# M706H.net
KiCad netlist of a schematic drawn in EAGLE
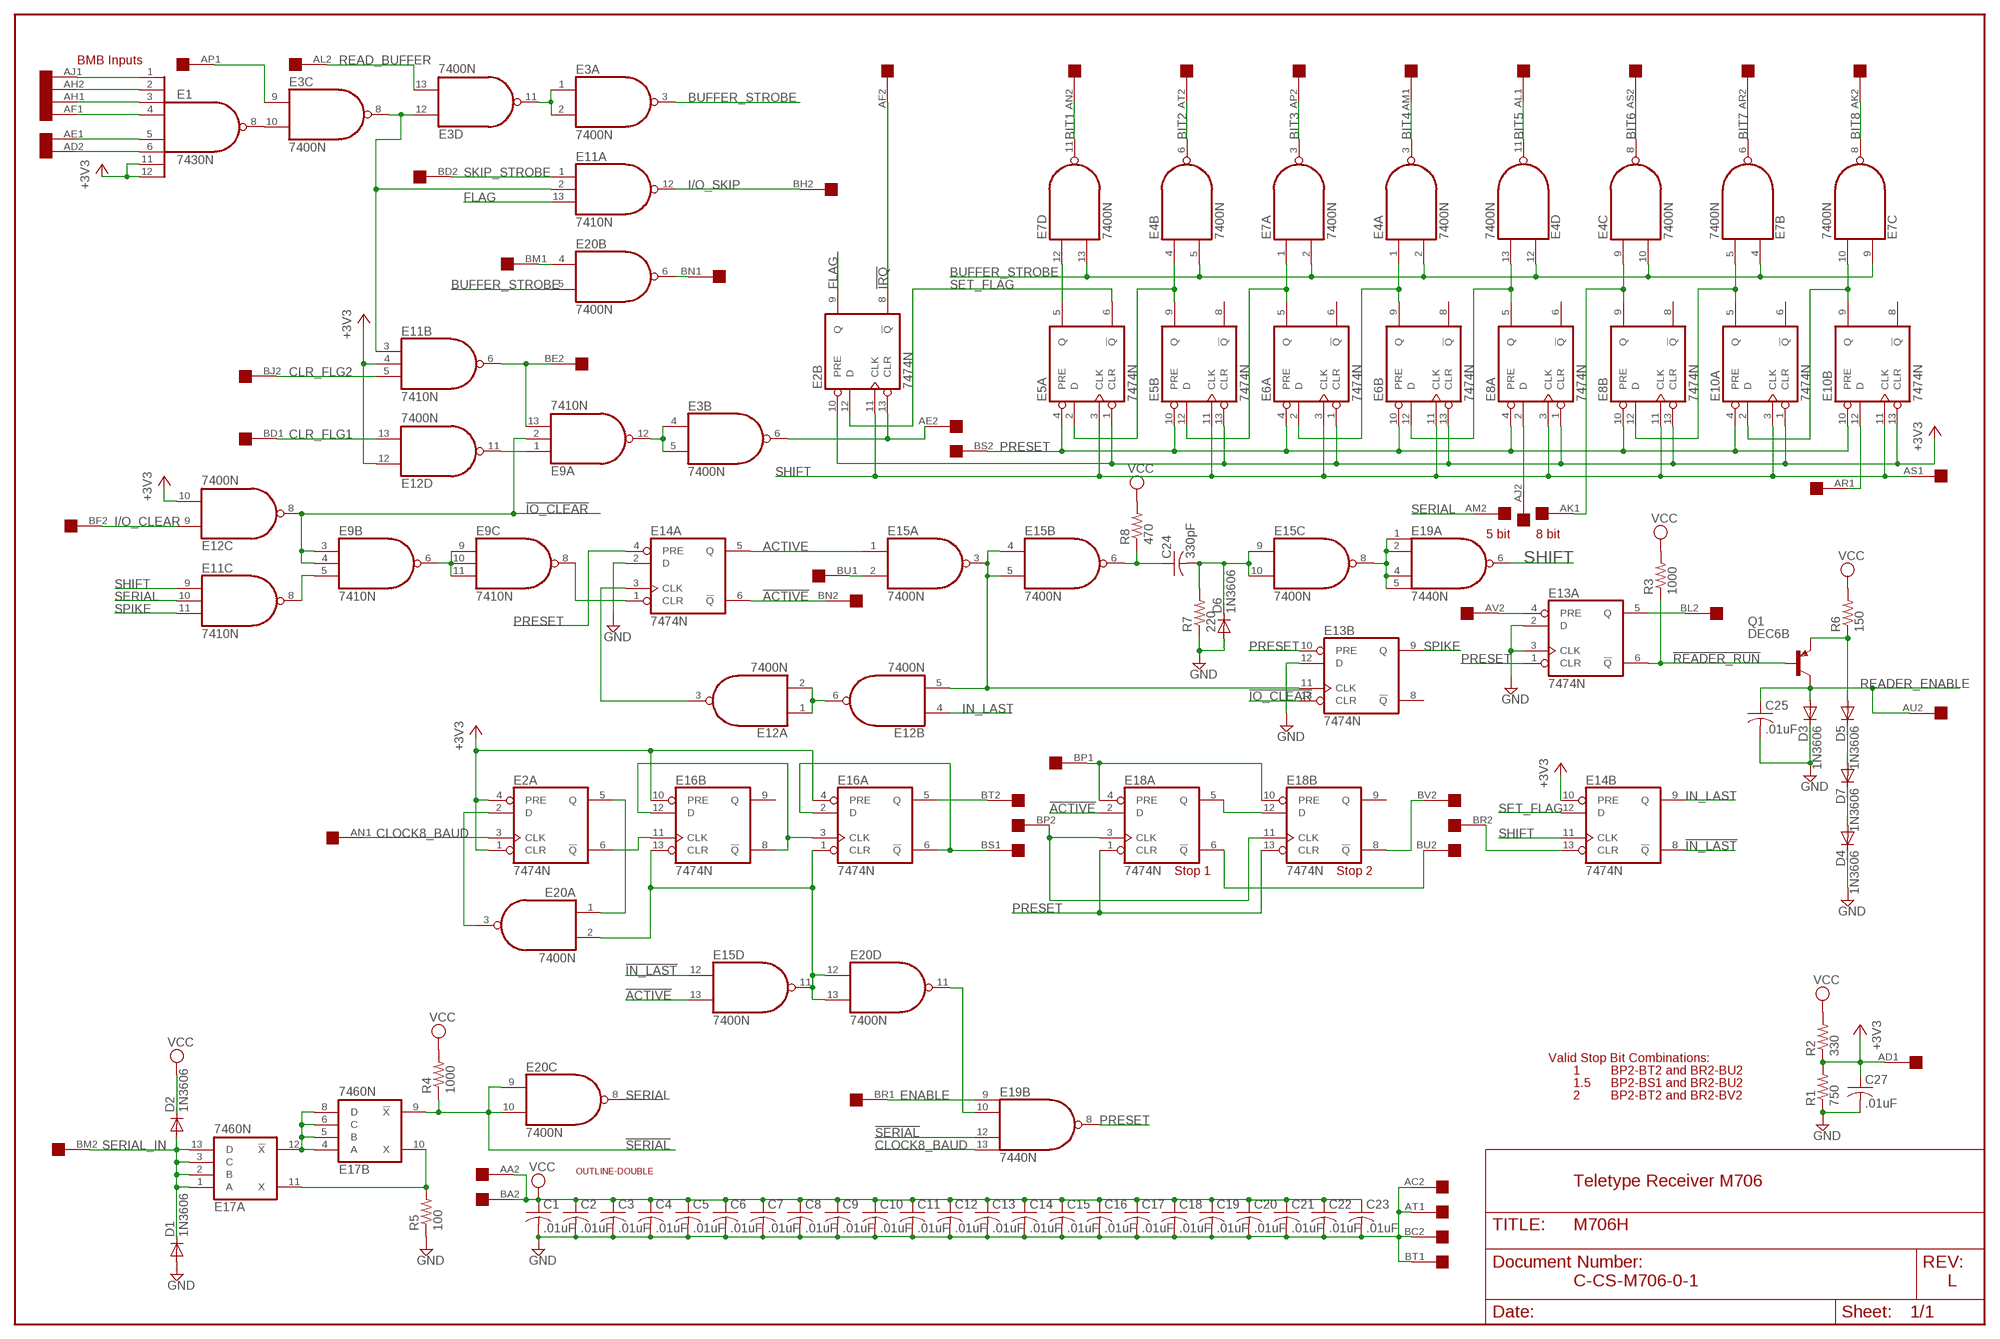
[diagram p0: schematic, sheet 1]

(export (version "E")
  (design (tool "Eeschema 10.0.6"))
  (components
    (comp (ref "C1")
      (value ".01uF")
      (footprint "eagle-import:C050-025X075")
      (libsource (lib "eagle-import") (part "C-US050-025X075"))
    )
    (comp (ref "C2")
      (value ".01uF")
      (footprint "eagle-import:C050-025X075")
      (libsource (lib "eagle-import") (part "C-US050-025X075"))
    )
    (comp (ref "C3")
      (value ".01uF")
      (footprint "eagle-import:C050-025X075")
      (libsource (lib "eagle-import") (part "C-US050-025X075"))
    )
    (comp (ref "C4")
      (value ".01uF")
      (footprint "eagle-import:C050-025X075")
      (libsource (lib "eagle-import") (part "C-US050-025X075"))
    )
    (comp (ref "C5")
      (value ".01uF")
      (footprint "eagle-import:C050-025X075")
      (libsource (lib "eagle-import") (part "C-US050-025X075"))
    )
    (comp (ref "C6")
      (value ".01uF")
      (footprint "eagle-import:C050-025X075")
      (libsource (lib "eagle-import") (part "C-US050-025X075"))
    )
    (comp (ref "C7")
      (value ".01uF")
      (footprint "eagle-import:C050-025X075")
      (libsource (lib "eagle-import") (part "C-US050-025X075"))
    )
    (comp (ref "C8")
      (value ".01uF")
      (footprint "eagle-import:C050-025X075")
      (libsource (lib "eagle-import") (part "C-US050-025X075"))
    )
    (comp (ref "C9")
      (value ".01uF")
      (footprint "eagle-import:C050-025X075")
      (libsource (lib "eagle-import") (part "C-US050-025X075"))
    )
    (comp (ref "C10")
      (value ".01uF")
      (footprint "eagle-import:C050-025X075")
      (libsource (lib "eagle-import") (part "C-US050-025X075"))
    )
    (comp (ref "C11")
      (value ".01uF")
      (footprint "eagle-import:C050-025X075")
      (libsource (lib "eagle-import") (part "C-US050-025X075"))
    )
    (comp (ref "C12")
      (value ".01uF")
      (footprint "eagle-import:C050-025X075")
      (libsource (lib "eagle-import") (part "C-US050-025X075"))
    )
    (comp (ref "C13")
      (value ".01uF")
      (footprint "eagle-import:C050-025X075")
      (libsource (lib "eagle-import") (part "C-US050-025X075"))
    )
    (comp (ref "C14")
      (value ".01uF")
      (footprint "eagle-import:C050-025X075")
      (libsource (lib "eagle-import") (part "C-US050-025X075"))
    )
    (comp (ref "C15")
      (value ".01uF")
      (footprint "eagle-import:C050-025X075")
      (libsource (lib "eagle-import") (part "C-US050-025X075"))
    )
    (comp (ref "C16")
      (value ".01uF")
      (footprint "eagle-import:C050-025X075")
      (libsource (lib "eagle-import") (part "C-US050-025X075"))
    )
    (comp (ref "C17")
      (value ".01uF")
      (footprint "eagle-import:C050-025X075")
      (libsource (lib "eagle-import") (part "C-US050-025X075"))
    )
    (comp (ref "C18")
      (value ".01uF")
      (footprint "eagle-import:C050-025X075")
      (libsource (lib "eagle-import") (part "C-US050-025X075"))
    )
    (comp (ref "C19")
      (value ".01uF")
      (footprint "eagle-import:C050-025X075")
      (libsource (lib "eagle-import") (part "C-US050-025X075"))
    )
    (comp (ref "C20")
      (value ".01uF")
      (footprint "eagle-import:C050-025X075")
      (libsource (lib "eagle-import") (part "C-US050-025X075"))
    )
    (comp (ref "C21")
      (value ".01uF")
      (footprint "eagle-import:C050-025X075")
      (libsource (lib "eagle-import") (part "C-US050-025X075"))
    )
    (comp (ref "C22")
      (value ".01uF")
      (footprint "eagle-import:C050-025X075")
      (libsource (lib "eagle-import") (part "C-US050-025X075"))
    )
    (comp (ref "C23")
      (value ".01uF")
      (footprint "eagle-import:C050-025X075")
      (libsource (lib "eagle-import") (part "C-US050-025X075"))
    )
    (comp (ref "C24")
      (value "330pF")
      (footprint "eagle-import:C050-025X075")
      (libsource (lib "eagle-import") (part "C-US050-025X075"))
    )
    (comp (ref "C25")
      (value ".01uF")
      (footprint "eagle-import:C050-025X075")
      (libsource (lib "eagle-import") (part "C-US050-025X075"))
    )
    (comp (ref "C27")
      (value ".01uF")
      (footprint "eagle-import:C050-025X075")
      (libsource (lib "eagle-import") (part "C-US050-025X075"))
    )
    (comp (ref "D1")
      (value "1N3606")
      (footprint "eagle-import:DO35-10")
      (libsource (lib "eagle-import") (part "1N4148DO35-10"))
    )
    (comp (ref "D2")
      (value "1N3606")
      (footprint "eagle-import:DO35-10")
      (libsource (lib "eagle-import") (part "1N4148DO35-10"))
    )
    (comp (ref "D3")
      (value "1N3606")
      (footprint "eagle-import:DO35-10")
      (libsource (lib "eagle-import") (part "1N4148DO35-10"))
    )
    (comp (ref "D4")
      (value "1N3606")
      (footprint "eagle-import:DO35-10")
      (libsource (lib "eagle-import") (part "1N4148DO35-10"))
    )
    (comp (ref "D5")
      (value "1N3606")
      (footprint "eagle-import:DO35-10")
      (libsource (lib "eagle-import") (part "1N4148DO35-10"))
    )
    (comp (ref "D6")
      (value "1N3606")
      (footprint "eagle-import:DO35-10")
      (libsource (lib "eagle-import") (part "1N4148DO35-10"))
    )
    (comp (ref "D7")
      (value "1N3606")
      (footprint "eagle-import:DO35-10")
      (libsource (lib "eagle-import") (part "1N4148DO35-10"))
    )
    (comp (ref "E1")
      (value "7430N")
      (footprint "eagle-import:DIL14")
      (libsource (lib "eagle-import") (part "7430N"))
    )
    (comp (ref "E2")
      (value "7474N")
      (footprint "eagle-import:DIL14")
      (libsource (lib "eagle-import") (part "7474NS"))
    )
    (comp (ref "E3")
      (value "7400N")
      (footprint "eagle-import:DIL14")
      (libsource (lib "eagle-import") (part "7400N"))
    )
    (comp (ref "E4")
      (value "7400N")
      (footprint "eagle-import:DIL14")
      (libsource (lib "eagle-import") (part "7400N"))
    )
    (comp (ref "E5")
      (value "7474N")
      (footprint "eagle-import:DIL14")
      (libsource (lib "eagle-import") (part "7474NS"))
    )
    (comp (ref "E6")
      (value "7474N")
      (footprint "eagle-import:DIL14")
      (libsource (lib "eagle-import") (part "7474NS"))
    )
    (comp (ref "E7")
      (value "7400N")
      (footprint "eagle-import:DIL14")
      (libsource (lib "eagle-import") (part "7400N"))
    )
    (comp (ref "E8")
      (value "7474N")
      (footprint "eagle-import:DIL14")
      (libsource (lib "eagle-import") (part "7474NS"))
    )
    (comp (ref "E9")
      (value "7410N")
      (footprint "eagle-import:DIL14")
      (libsource (lib "eagle-import") (part "7410N"))
    )
    (comp (ref "E10")
      (value "7474N")
      (footprint "eagle-import:DIL14")
      (libsource (lib "eagle-import") (part "7474NS"))
    )
    (comp (ref "E11")
      (value "7410N")
      (footprint "eagle-import:DIL14")
      (libsource (lib "eagle-import") (part "7410N"))
    )
    (comp (ref "E12")
      (value "7400N")
      (footprint "eagle-import:DIL14")
      (libsource (lib "eagle-import") (part "7400N"))
    )
    (comp (ref "E13")
      (value "7474N")
      (footprint "eagle-import:DIL14")
      (libsource (lib "eagle-import") (part "7474NS"))
    )
    (comp (ref "E14")
      (value "7474N")
      (footprint "eagle-import:DIL14")
      (libsource (lib "eagle-import") (part "7474NS"))
    )
    (comp (ref "E15")
      (value "7400N")
      (footprint "eagle-import:DIL14")
      (libsource (lib "eagle-import") (part "7400N"))
    )
    (comp (ref "E16")
      (value "7474N")
      (footprint "eagle-import:DIL14")
      (libsource (lib "eagle-import") (part "7474NS"))
    )
    (comp (ref "E17")
      (value "7460N")
      (footprint "eagle-import:DIL14")
      (libsource (lib "eagle-import") (part "7460N"))
    )
    (comp (ref "E18")
      (value "7474N")
      (footprint "eagle-import:DIL14")
      (libsource (lib "eagle-import") (part "7474NS"))
    )
    (comp (ref "E19")
      (value "7440N")
      (footprint "eagle-import:DIL14")
      (libsource (lib "eagle-import") (part "7420NS"))
    )
    (comp (ref "E20")
      (value "7400N")
      (footprint "eagle-import:DIL14")
      (libsource (lib "eagle-import") (part "7400N"))
    )
    (comp (ref "Q1")
      (value "DEC6B")
      (footprint "eagle-import:TO39")
      (libsource (lib "eagle-import") (part "2N2904"))
    )
    (comp (ref "R1")
      (value "750")
      (footprint "eagle-import:0207_10")
      (libsource (lib "eagle-import") (part "R-US_0207/10"))
    )
    (comp (ref "R2")
      (value "330")
      (footprint "eagle-import:0207_10")
      (libsource (lib "eagle-import") (part "R-US_0207/10"))
    )
    (comp (ref "R3")
      (value "1000")
      (footprint "eagle-import:0207_10")
      (libsource (lib "eagle-import") (part "R-US_0207/10"))
    )
    (comp (ref "R4")
      (value "1000")
      (footprint "eagle-import:0207_10")
      (libsource (lib "eagle-import") (part "R-US_0207/10"))
    )
    (comp (ref "R5")
      (value "100")
      (footprint "eagle-import:0207_10")
      (libsource (lib "eagle-import") (part "R-US_0207/10"))
    )
    (comp (ref "R6")
      (value "150")
      (footprint "eagle-import:0207_10")
      (libsource (lib "eagle-import") (part "R-US_0207/10"))
    )
    (comp (ref "R7")
      (value "220")
      (footprint "eagle-import:0207_10")
      (libsource (lib "eagle-import") (part "R-US_0207/10"))
    )
    (comp (ref "R8")
      (value "470")
      (footprint "eagle-import:0207_10")
      (libsource (lib "eagle-import") (part "R-US_0207/10"))
    )
    (comp (ref "U$1")
      (value "OUTLINE-DOUBLE")
      (footprint "eagle-import:DOUBLE")
      (libsource (lib "eagle-import") (part "OUTLINE-DOUBLE"))
    )
    (comp (ref "U$2")
      (value "DOUBLE")
      (footprint "eagle-import:EDGE-CON4")
      (libsource (lib "eagle-import") (part "DOUBLE"))
    )
  )
  (nets
    (net (code "1") (name "+3V3") (class "Default")
      (node (ref "C27") (pin "1") (pinfunction "1_1") (pintype "passive"))
      (node (ref "E1") (pin "11") (pinfunction "I6_11") (pintype "input"))
      (node (ref "E1") (pin "12") (pinfunction "I7_12") (pintype "input"))
      (node (ref "E10") (pin "1") (pinfunction "CLR_1") (pintype "input"))
      (node (ref "E10") (pin "13") (pinfunction "CLR_13") (pintype "input"))
      (node (ref "E11") (pin "4") (pinfunction "I1_4") (pintype "input"))
      (node (ref "E12") (pin "10") (pinfunction "I1_10") (pintype "input"))
      (node (ref "E12") (pin "12") (pinfunction "I0_12") (pintype "input"))
      (node (ref "E14") (pin "10") (pinfunction "PRE_10") (pintype "input"))
      (node (ref "E16") (pin "10") (pinfunction "PRE_10") (pintype "input"))
      (node (ref "E16") (pin "4") (pinfunction "PRE_4") (pintype "input"))
      (node (ref "E2") (pin "1") (pinfunction "CLR_1") (pintype "input"))
      (node (ref "E2") (pin "10") (pinfunction "PRE_10") (pintype "input"))
      (node (ref "E2") (pin "4") (pinfunction "PRE_4") (pintype "input"))
      (node (ref "E5") (pin "1") (pinfunction "CLR_1") (pintype "input"))
      (node (ref "E5") (pin "13") (pinfunction "CLR_13") (pintype "input"))
      (node (ref "E6") (pin "1") (pinfunction "CLR_1") (pintype "input"))
      (node (ref "E6") (pin "13") (pinfunction "CLR_13") (pintype "input"))
      (node (ref "E8") (pin "1") (pinfunction "CLR_1") (pintype "input"))
      (node (ref "E8") (pin "13") (pinfunction "CLR_13") (pintype "input"))
      (node (ref "R1") (pin "2") (pinfunction "2_2") (pintype "passive"))
      (node (ref "R2") (pin "1") (pinfunction "1_1") (pintype "passive"))
      (node (ref "U$2") (pin "AD1") (pinfunction "1_AD1") (pintype "bidirectional"))
    )
    (net (code "2") (name "/ACTIVE") (class "Default")
      (node (ref "E14") (pin "5") (pinfunction "Q_5") (pintype "output"))
      (node (ref "E15") (pin "1") (pinfunction "I0_1") (pintype "input"))
    )
    (net (code "3") (name "/BIT1") (class "Default")
      (node (ref "E7") (pin "11") (pinfunction "O_11") (pintype "output"))
      (node (ref "U$2") (pin "AN2") (pinfunction "1_AN2") (pintype "bidirectional"))
    )
    (net (code "4") (name "/BIT2") (class "Default")
      (node (ref "E4") (pin "6") (pinfunction "O_6") (pintype "output"))
      (node (ref "U$2") (pin "AT2") (pinfunction "1_AT2") (pintype "bidirectional"))
    )
    (net (code "5") (name "/BIT3") (class "Default")
      (node (ref "E7") (pin "3") (pinfunction "O_3") (pintype "output"))
      (node (ref "U$2") (pin "AP2") (pinfunction "1_AP2") (pintype "bidirectional"))
    )
    (net (code "6") (name "/BIT4") (class "Default")
      (node (ref "E4") (pin "3") (pinfunction "O_3") (pintype "output"))
      (node (ref "U$2") (pin "AM1") (pinfunction "1_AM1") (pintype "bidirectional"))
    )
    (net (code "7") (name "/BIT5") (class "Default")
      (node (ref "E4") (pin "11") (pinfunction "O_11") (pintype "output"))
      (node (ref "U$2") (pin "AL1") (pinfunction "1_AL1") (pintype "bidirectional"))
    )
    (net (code "8") (name "/BIT6") (class "Default")
      (node (ref "E4") (pin "8") (pinfunction "O_8") (pintype "output"))
      (node (ref "U$2") (pin "AS2") (pinfunction "1_AS2") (pintype "bidirectional"))
    )
    (net (code "9") (name "/BIT7") (class "Default")
      (node (ref "E7") (pin "6") (pinfunction "O_6") (pintype "output"))
      (node (ref "U$2") (pin "AR2") (pinfunction "1_AR2") (pintype "bidirectional"))
    )
    (net (code "10") (name "/BIT8") (class "Default")
      (node (ref "E7") (pin "8") (pinfunction "O_8") (pintype "output"))
      (node (ref "U$2") (pin "AK2") (pinfunction "1_AK2") (pintype "bidirectional"))
    )
    (net (code "11") (name "/BUFFER_STROBE") (class "Default")
      (node (ref "E20") (pin "5") (pinfunction "I1_5") (pintype "input"))
      (node (ref "E3") (pin "3") (pinfunction "O_3") (pintype "output"))
      (node (ref "E4") (pin "10") (pinfunction "I1_10") (pintype "input"))
      (node (ref "E4") (pin "12") (pinfunction "I0_12") (pintype "input"))
      (node (ref "E4") (pin "2") (pinfunction "I1_2") (pintype "input"))
      (node (ref "E4") (pin "5") (pinfunction "I1_5") (pintype "input"))
      (node (ref "E7") (pin "13") (pinfunction "I1_13") (pintype "input"))
      (node (ref "E7") (pin "2") (pinfunction "I1_2") (pintype "input"))
      (node (ref "E7") (pin "4") (pinfunction "I0_4") (pintype "input"))
      (node (ref "E7") (pin "9") (pinfunction "I0_9") (pintype "input"))
    )
    (net (code "12") (name "/CLOCK8_BAUD") (class "Default")
      (node (ref "E19") (pin "13") (pinfunction "I3_13") (pintype "input"))
      (node (ref "E2") (pin "3") (pinfunction "CLK_3") (pintype "input"))
      (node (ref "U$2") (pin "AN1") (pinfunction "1_AN1") (pintype "bidirectional"))
    )
    (net (code "13") (name "/CLR_FLG1") (class "Default")
      (node (ref "E12") (pin "13") (pinfunction "I1_13") (pintype "input"))
      (node (ref "U$2") (pin "BD1") (pinfunction "1_BD1") (pintype "bidirectional"))
    )
    (net (code "14") (name "/CLR_FLG2") (class "Default")
      (node (ref "E11") (pin "5") (pinfunction "I2_5") (pintype "input"))
      (node (ref "U$2") (pin "BJ2") (pinfunction "1_BJ2") (pintype "bidirectional"))
    )
    (net (code "15") (name "/ENABLE") (class "Default")
      (node (ref "E19") (pin "9") (pinfunction "I0_9") (pintype "input"))
      (node (ref "U$2") (pin "BR1") (pinfunction "1_BR1") (pintype "bidirectional"))
    )
    (net (code "16") (name "/FLAG") (class "Default")
      (node (ref "E11") (pin "13") (pinfunction "I2_13") (pintype "input"))
      (node (ref "E2") (pin "9") (pinfunction "Q_9") (pintype "output"))
    )
    (net (code "17") (name "/IN_LAST") (class "Default")
      (node (ref "E12") (pin "4") (pinfunction "I0_4") (pintype "input"))
      (node (ref "E14") (pin "9") (pinfunction "Q_9") (pintype "output"))
    )
    (net (code "18") (name "/I{slash}O_CLEAR") (class "Default")
      (node (ref "E12") (pin "9") (pinfunction "I0_9") (pintype "input"))
      (node (ref "U$2") (pin "BF2") (pinfunction "1_BF2") (pintype "bidirectional"))
    )
    (net (code "19") (name "/I{slash}O_SKIP") (class "Default")
      (node (ref "E11") (pin "12") (pinfunction "O_12") (pintype "output"))
      (node (ref "U$2") (pin "BH2") (pinfunction "1_BH2") (pintype "bidirectional"))
    )
    (net (code "20") (name "/PRESET") (class "Default")
      (node (ref "E10") (pin "10") (pinfunction "PRE_10") (pintype "input"))
      (node (ref "E10") (pin "4") (pinfunction "PRE_4") (pintype "input"))
      (node (ref "E13") (pin "1") (pinfunction "CLR_1") (pintype "input"))
      (node (ref "E13") (pin "10") (pinfunction "PRE_10") (pintype "input"))
      (node (ref "E14") (pin "4") (pinfunction "PRE_4") (pintype "input"))
      (node (ref "E18") (pin "1") (pinfunction "CLR_1") (pintype "input"))
      (node (ref "E18") (pin "13") (pinfunction "CLR_13") (pintype "input"))
      (node (ref "E19") (pin "8") (pinfunction "O_8") (pintype "output"))
      (node (ref "E5") (pin "10") (pinfunction "PRE_10") (pintype "input"))
      (node (ref "E5") (pin "4") (pinfunction "PRE_4") (pintype "input"))
      (node (ref "E6") (pin "10") (pinfunction "PRE_10") (pintype "input"))
      (node (ref "E6") (pin "4") (pinfunction "PRE_4") (pintype "input"))
      (node (ref "E8") (pin "10") (pinfunction "PRE_10") (pintype "input"))
      (node (ref "E8") (pin "4") (pinfunction "PRE_4") (pintype "input"))
      (node (ref "U$2") (pin "BS2") (pinfunction "1_BS2") (pintype "bidirectional"))
    )
    (net (code "21") (name "/READER_ENABLE") (class "Default")
      (node (ref "C25") (pin "1") (pinfunction "1_1") (pintype "passive"))
      (node (ref "D3") (pin "A") (pinfunction "A_A") (pintype "passive"))
      (node (ref "Q1") (pin "3") (pinfunction "C_3") (pintype "passive"))
      (node (ref "U$2") (pin "AU2") (pinfunction "1_AU2") (pintype "bidirectional"))
    )
    (net (code "22") (name "/READ_BUFFER") (class "Default")
      (node (ref "E3") (pin "13") (pinfunction "I1_13") (pintype "input"))
      (node (ref "U$2") (pin "AL2") (pinfunction "1_AL2") (pintype "bidirectional"))
    )
    (net (code "23") (name "/SERIAL") (class "Default")
      (node (ref "E11") (pin "10") (pinfunction "I1_10") (pintype "input"))
      (node (ref "E20") (pin "8") (pinfunction "O_8") (pintype "output"))
      (node (ref "U$2") (pin "AM2") (pinfunction "1_AM2") (pintype "bidirectional"))
    )
    (net (code "24") (name "/SERIAL_IN") (class "Default")
      (node (ref "D1") (pin "C") (pinfunction "C_C") (pintype "passive"))
      (node (ref "D2") (pin "A") (pinfunction "A_A") (pintype "passive"))
      (node (ref "E17") (pin "1") (pinfunction "A_1") (pintype "input"))
      (node (ref "E17") (pin "13") (pinfunction "D_13") (pintype "input"))
      (node (ref "E17") (pin "2") (pinfunction "B_2") (pintype "input"))
      (node (ref "E17") (pin "3") (pinfunction "C_3") (pintype "input"))
      (node (ref "U$2") (pin "BM2") (pinfunction "1_BM2") (pintype "bidirectional"))
    )
    (net (code "25") (name "/SET_FLAG") (class "Default")
      (node (ref "E14") (pin "12") (pinfunction "D_12") (pintype "input"))
      (node (ref "E2") (pin "12") (pinfunction "D_12") (pintype "input"))
      (node (ref "E5") (pin "6") (pinfunction "~{Q}_6") (pintype "output"))
    )
    (net (code "26") (name "/SHIFT") (class "Default")
      (node (ref "E10") (pin "11") (pinfunction "CLK_11") (pintype "input"))
      (node (ref "E10") (pin "3") (pinfunction "CLK_3") (pintype "input"))
      (node (ref "E11") (pin "9") (pinfunction "I0_9") (pintype "input"))
      (node (ref "E14") (pin "11") (pinfunction "CLK_11") (pintype "input"))
      (node (ref "E19") (pin "6") (pinfunction "O_6") (pintype "output"))
      (node (ref "E2") (pin "11") (pinfunction "CLK_11") (pintype "input"))
      (node (ref "E5") (pin "11") (pinfunction "CLK_11") (pintype "input"))
      (node (ref "E5") (pin "3") (pinfunction "CLK_3") (pintype "input"))
      (node (ref "E6") (pin "11") (pinfunction "CLK_11") (pintype "input"))
      (node (ref "E6") (pin "3") (pinfunction "CLK_3") (pintype "input"))
      (node (ref "E8") (pin "11") (pinfunction "CLK_11") (pintype "input"))
      (node (ref "E8") (pin "3") (pinfunction "CLK_3") (pintype "input"))
      (node (ref "U$2") (pin "AS1") (pinfunction "1_AS1") (pintype "bidirectional"))
    )
    (net (code "27") (name "/SKIP_STROBE") (class "Default")
      (node (ref "E11") (pin "1") (pinfunction "I0_1") (pintype "input"))
      (node (ref "U$2") (pin "BD2") (pinfunction "1_BD2") (pintype "bidirectional"))
    )
    (net (code "28") (name "/SPIKE") (class "Default")
      (node (ref "E11") (pin "11") (pinfunction "I2_11") (pintype "input"))
      (node (ref "E13") (pin "9") (pinfunction "Q_9") (pintype "output"))
    )
    (net (code "29") (name "/~{ACTIVE}") (class "Default")
      (node (ref "E14") (pin "6") (pinfunction "~{Q}_6") (pintype "output"))
      (node (ref "E15") (pin "13") (pinfunction "I1_13") (pintype "input"))
      (node (ref "E18") (pin "2") (pinfunction "D_2") (pintype "input"))
      (node (ref "U$2") (pin "BN2") (pinfunction "1_BN2") (pintype "bidirectional"))
    )
    (net (code "30") (name "/~{IN_LAST}") (class "Default")
      (node (ref "E14") (pin "8") (pinfunction "~{Q}_8") (pintype "output"))
      (node (ref "E15") (pin "12") (pinfunction "I0_12") (pintype "input"))
    )
    (net (code "31") (name "/~{IO_CLEAR}") (class "Default")
      (node (ref "E12") (pin "8") (pinfunction "O_8") (pintype "output"))
      (node (ref "E13") (pin "13") (pinfunction "CLR_13") (pintype "input"))
      (node (ref "E9") (pin "2") (pinfunction "I1_2") (pintype "input"))
      (node (ref "E9") (pin "3") (pinfunction "I0_3") (pintype "input"))
      (node (ref "E9") (pin "4") (pinfunction "I1_4") (pintype "input"))
    )
    (net (code "32") (name "/~{IRQ}") (class "Default")
      (node (ref "E2") (pin "8") (pinfunction "~{Q}_8") (pintype "output"))
      (node (ref "U$2") (pin "AF2") (pinfunction "1_AF2") (pintype "bidirectional"))
    )
    (net (code "33") (name "/~{READER_RUN}") (class "Default")
      (node (ref "E13") (pin "6") (pinfunction "~{Q}_6") (pintype "output"))
      (node (ref "Q1") (pin "2") (pinfunction "B_2") (pintype "passive"))
      (node (ref "R3") (pin "1") (pinfunction "1_1") (pintype "passive"))
    )
    (net (code "34") (name "/~{SERIAL}") (class "Default")
      (node (ref "E17") (pin "9") (pinfunction "~{X}_9") (pintype "output"))
      (node (ref "E19") (pin "12") (pinfunction "I2_12") (pintype "input"))
      (node (ref "E20") (pin "10") (pinfunction "I1_10") (pintype "input"))
      (node (ref "E20") (pin "9") (pinfunction "I0_9") (pintype "input"))
      (node (ref "R4") (pin "1") (pinfunction "1_1") (pintype "passive"))
    )
    (net (code "35") (name "GND") (class "Default")
      (node (ref "C1") (pin "2") (pinfunction "2_2") (pintype "passive"))
      (node (ref "C10") (pin "2") (pinfunction "2_2") (pintype "passive"))
      (node (ref "C11") (pin "2") (pinfunction "2_2") (pintype "passive"))
      (node (ref "C12") (pin "2") (pinfunction "2_2") (pintype "passive"))
      (node (ref "C13") (pin "2") (pinfunction "2_2") (pintype "passive"))
      (node (ref "C14") (pin "2") (pinfunction "2_2") (pintype "passive"))
      (node (ref "C15") (pin "2") (pinfunction "2_2") (pintype "passive"))
      (node (ref "C16") (pin "2") (pinfunction "2_2") (pintype "passive"))
      (node (ref "C17") (pin "2") (pinfunction "2_2") (pintype "passive"))
      (node (ref "C18") (pin "2") (pinfunction "2_2") (pintype "passive"))
      (node (ref "C19") (pin "2") (pinfunction "2_2") (pintype "passive"))
      (node (ref "C2") (pin "2") (pinfunction "2_2") (pintype "passive"))
      (node (ref "C20") (pin "2") (pinfunction "2_2") (pintype "passive"))
      (node (ref "C21") (pin "2") (pinfunction "2_2") (pintype "passive"))
      (node (ref "C22") (pin "2") (pinfunction "2_2") (pintype "passive"))
      (node (ref "C23") (pin "2") (pinfunction "2_2") (pintype "passive"))
      (node (ref "C25") (pin "2") (pinfunction "2_2") (pintype "passive"))
      (node (ref "C27") (pin "2") (pinfunction "2_2") (pintype "passive"))
      (node (ref "C3") (pin "2") (pinfunction "2_2") (pintype "passive"))
      (node (ref "C4") (pin "2") (pinfunction "2_2") (pintype "passive"))
      (node (ref "C5") (pin "2") (pinfunction "2_2") (pintype "passive"))
      (node (ref "C6") (pin "2") (pinfunction "2_2") (pintype "passive"))
      (node (ref "C7") (pin "2") (pinfunction "2_2") (pintype "passive"))
      (node (ref "C8") (pin "2") (pinfunction "2_2") (pintype "passive"))
      (node (ref "C9") (pin "2") (pinfunction "2_2") (pintype "passive"))
      (node (ref "D1") (pin "A") (pinfunction "A_A") (pintype "passive"))
      (node (ref "D3") (pin "C") (pinfunction "C_C") (pintype "passive"))
      (node (ref "D4") (pin "C") (pinfunction "C_C") (pintype "passive"))
      (node (ref "D6") (pin "A") (pinfunction "A_A") (pintype "passive"))
      (node (ref "E13") (pin "12") (pinfunction "D_12") (pintype "input"))
      (node (ref "E13") (pin "2") (pinfunction "D_2") (pintype "input"))
      (node (ref "E13") (pin "3") (pinfunction "CLK_3") (pintype "input"))
      (node (ref "E14") (pin "2") (pinfunction "D_2") (pintype "input"))
      (node (ref "R1") (pin "1") (pinfunction "1_1") (pintype "passive"))
      (node (ref "R5") (pin "1") (pinfunction "1_1") (pintype "passive"))
      (node (ref "R7") (pin "1") (pinfunction "1_1") (pintype "passive"))
      (node (ref "U$2") (pin "AC2") (pinfunction "1_AC2") (pintype "bidirectional"))
      (node (ref "U$2") (pin "AT1") (pinfunction "1_AT1") (pintype "bidirectional"))
      (node (ref "U$2") (pin "BC2") (pinfunction "1_BC2") (pintype "bidirectional"))
      (node (ref "U$2") (pin "BT1") (pinfunction "1_BT1") (pintype "bidirectional"))
    )
    (net (code "36") (name "Net-(D4-PadA)") (class "Default")
      (node (ref "D4") (pin "A") (pinfunction "A_A") (pintype "passive"))
      (node (ref "D7") (pin "C") (pinfunction "C_C") (pintype "passive"))
    )
    (net (code "37") (name "Net-(D5-PadC)") (class "Default")
      (node (ref "D5") (pin "C") (pinfunction "C_C") (pintype "passive"))
      (node (ref "D7") (pin "A") (pinfunction "A_A") (pintype "passive"))
    )
    (net (code "38") (name "Net-(E1A-I0)") (class "Default")
      (node (ref "E1") (pin "1") (pinfunction "I0_1") (pintype "input"))
      (node (ref "U$2") (pin "AJ1") (pinfunction "1_AJ1") (pintype "bidirectional"))
    )
    (net (code "39") (name "Net-(E1A-I1)") (class "Default")
      (node (ref "E1") (pin "2") (pinfunction "I1_2") (pintype "input"))
      (node (ref "U$2") (pin "AH2") (pinfunction "1_AH2") (pintype "bidirectional"))
    )
    (net (code "40") (name "Net-(E1A-I2)") (class "Default")
      (node (ref "E1") (pin "3") (pinfunction "I2_3") (pintype "input"))
      (node (ref "U$2") (pin "AH1") (pinfunction "1_AH1") (pintype "bidirectional"))
    )
    (net (code "41") (name "Net-(E1A-I3)") (class "Default")
      (node (ref "E1") (pin "4") (pinfunction "I3_4") (pintype "input"))
      (node (ref "U$2") (pin "AF1") (pinfunction "1_AF1") (pintype "bidirectional"))
    )
    (net (code "42") (name "Net-(E1A-I4)") (class "Default")
      (node (ref "E1") (pin "5") (pinfunction "I4_5") (pintype "input"))
      (node (ref "U$2") (pin "AE1") (pinfunction "1_AE1") (pintype "bidirectional"))
    )
    (net (code "43") (name "Net-(E1A-I5)") (class "Default")
      (node (ref "E1") (pin "6") (pinfunction "I5_6") (pintype "input"))
      (node (ref "U$2") (pin "AD2") (pinfunction "1_AD2") (pintype "bidirectional"))
    )
    (net (code "44") (name "Net-(E1A-O)") (class "Default")
      (node (ref "E1") (pin "8") (pinfunction "O_8") (pintype "output"))
      (node (ref "E3") (pin "10") (pinfunction "I1_10") (pintype "input"))
    )
    (net (code "45") (name "Net-(E2B-CLR)") (class "Default")
      (node (ref "E2") (pin "13") (pinfunction "CLR_13") (pintype "input"))
      (node (ref "E3") (pin "6") (pinfunction "O_6") (pintype "output"))
      (node (ref "U$2") (pin "AE2") (pinfunction "1_AE2") (pintype "bidirectional"))
    )
    (net (code "46") (name "Net-(E3A-I0)") (class "Default")
      (node (ref "E3") (pin "1") (pinfunction "I0_1") (pintype "input"))
      (node (ref "E3") (pin "11") (pinfunction "O_11") (pintype "output"))
      (node (ref "E3") (pin "2") (pinfunction "I1_2") (pintype "input"))
    )
    (net (code "47") (name "Net-(E3B-I0)") (class "Default")
      (node (ref "E3") (pin "4") (pinfunction "I0_4") (pintype "input"))
      (node (ref "E3") (pin "5") (pinfunction "I1_5") (pintype "input"))
      (node (ref "E9") (pin "12") (pinfunction "O_12") (pintype "output"))
    )
    (net (code "48") (name "Net-(E3C-I0)") (class "Default")
      (node (ref "E3") (pin "9") (pinfunction "I0_9") (pintype "input"))
      (node (ref "U$2") (pin "AP1") (pinfunction "1_AP1") (pintype "bidirectional"))
    )
    (net (code "49") (name "Net-(E4A-I0)") (class "Default")
      (node (ref "E4") (pin "1") (pinfunction "I0_1") (pintype "input"))
      (node (ref "E6") (pin "2") (pinfunction "D_2") (pintype "input"))
      (node (ref "E6") (pin "9") (pinfunction "Q_9") (pintype "output"))
    )
    (net (code "50") (name "Net-(E4B-I0)") (class "Default")
      (node (ref "E4") (pin "4") (pinfunction "I0_4") (pintype "input"))
      (node (ref "E5") (pin "2") (pinfunction "D_2") (pintype "input"))
      (node (ref "E5") (pin "9") (pinfunction "Q_9") (pintype "output"))
    )
    (net (code "51") (name "Net-(E4C-I0)") (class "Default")
      (node (ref "E4") (pin "9") (pinfunction "I0_9") (pintype "input"))
      (node (ref "E8") (pin "9") (pinfunction "Q_9") (pintype "output"))
      (node (ref "U$2") (pin "AK1") (pinfunction "1_AK1") (pintype "bidirectional"))
    )
    (net (code "52") (name "Net-(E4D-I1)") (class "Default")
      (node (ref "E4") (pin "13") (pinfunction "I1_13") (pintype "input"))
      (node (ref "E6") (pin "12") (pinfunction "D_12") (pintype "input"))
      (node (ref "E8") (pin "5") (pinfunction "Q_5") (pintype "output"))
    )
    (net (code "53") (name "Net-(E5A-Q)") (class "Default")
      (node (ref "E5") (pin "5") (pinfunction "Q_5") (pintype "output"))
      (node (ref "E7") (pin "12") (pinfunction "I0_12") (pintype "input"))
    )
    (net (code "54") (name "Net-(E5B-D)") (class "Default")
      (node (ref "E5") (pin "12") (pinfunction "D_12") (pintype "input"))
      (node (ref "E6") (pin "5") (pinfunction "Q_5") (pintype "output"))
      (node (ref "E7") (pin "1") (pinfunction "I0_1") (pintype "input"))
    )
    (net (code "55") (name "Net-(E8A-D)") (class "Default")
      (node (ref "E8") (pin "2") (pinfunction "D_2") (pintype "input"))
      (node (ref "U$2") (pin "AJ2") (pinfunction "1_AJ2") (pintype "bidirectional"))
    )
    (net (code "56") (name "Net-(E9B-O)") (class "Default")
      (node (ref "E9") (pin "10") (pinfunction "I1_10") (pintype "input"))
      (node (ref "E9") (pin "11") (pinfunction "I2_11") (pintype "input"))
      (node (ref "E9") (pin "6") (pinfunction "O_6") (pintype "output"))
      (node (ref "E9") (pin "9") (pinfunction "I0_9") (pintype "input"))
    )
    (net (code "57") (name "Net-(E10A-D)") (class "Default")
      (node (ref "E10") (pin "2") (pinfunction "D_2") (pintype "input"))
      (node (ref "E10") (pin "9") (pinfunction "Q_9") (pintype "output"))
      (node (ref "E7") (pin "10") (pinfunction "I1_10") (pintype "input"))
    )
    (net (code "58") (name "Net-(E10A-Q)") (class "Default")
      (node (ref "E10") (pin "5") (pinfunction "Q_5") (pintype "output"))
      (node (ref "E7") (pin "5") (pinfunction "I1_5") (pintype "input"))
      (node (ref "E8") (pin "12") (pinfunction "D_12") (pintype "input"))
    )
    (net (code "59") (name "Net-(E10B-D)") (class "Default")
      (node (ref "E10") (pin "12") (pinfunction "D_12") (pintype "input"))
      (node (ref "U$2") (pin "AR1") (pinfunction "1_AR1") (pintype "bidirectional"))
    )
    (net (code "60") (name "Net-(E11A-I1)") (class "Default")
      (node (ref "E11") (pin "2") (pinfunction "I1_2") (pintype "input"))
      (node (ref "E11") (pin "3") (pinfunction "I0_3") (pintype "input"))
      (node (ref "E3") (pin "12") (pinfunction "I0_12") (pintype "input"))
      (node (ref "E3") (pin "8") (pinfunction "O_8") (pintype "output"))
    )
    (net (code "61") (name "Net-(E11B-O)") (class "Default")
      (node (ref "E11") (pin "6") (pinfunction "O_6") (pintype "output"))
      (node (ref "E9") (pin "13") (pinfunction "I2_13") (pintype "input"))
      (node (ref "U$2") (pin "BE2") (pinfunction "1_BE2") (pintype "bidirectional"))
    )
    (net (code "62") (name "Net-(E11C-O)") (class "Default")
      (node (ref "E11") (pin "8") (pinfunction "O_8") (pintype "output"))
      (node (ref "E9") (pin "5") (pinfunction "I2_5") (pintype "input"))
    )
    (net (code "63") (name "Net-(E12A-I0)") (class "Default")
      (node (ref "E12") (pin "1") (pinfunction "I0_1") (pintype "input"))
      (node (ref "E12") (pin "2") (pinfunction "I1_2") (pintype "input"))
      (node (ref "E12") (pin "6") (pinfunction "O_6") (pintype "output"))
    )
    (net (code "64") (name "Net-(E12A-O)") (class "Default")
      (node (ref "E12") (pin "3") (pinfunction "O_3") (pintype "output"))
      (node (ref "E14") (pin "3") (pinfunction "CLK_3") (pintype "input"))
    )
    (net (code "65") (name "Net-(E12B-I1)") (class "Default")
      (node (ref "E12") (pin "5") (pinfunction "I1_5") (pintype "input"))
      (node (ref "E13") (pin "11") (pinfunction "CLK_11") (pintype "input"))
      (node (ref "E15") (pin "3") (pinfunction "O_3") (pintype "output"))
      (node (ref "E15") (pin "4") (pinfunction "I0_4") (pintype "input"))
      (node (ref "E15") (pin "5") (pinfunction "I1_5") (pintype "input"))
    )
    (net (code "66") (name "Net-(E12D-O)") (class "Default")
      (node (ref "E12") (pin "11") (pinfunction "O_11") (pintype "output"))
      (node (ref "E9") (pin "1") (pinfunction "I0_1") (pintype "input"))
    )
    (net (code "67") (name "Net-(E13A-PRE)") (class "Default")
      (node (ref "E13") (pin "4") (pinfunction "PRE_4") (pintype "input"))
      (node (ref "U$2") (pin "AV2") (pinfunction "1_AV2") (pintype "bidirectional"))
    )
    (net (code "68") (name "Net-(E13A-Q)") (class "Default")
      (node (ref "E13") (pin "5") (pinfunction "Q_5") (pintype "output"))
      (node (ref "U$2") (pin "BL2") (pinfunction "1_BL2") (pintype "bidirectional"))
    )
    (net (code "69") (name "Net-(E14A-CLR)") (class "Default")
      (node (ref "E14") (pin "1") (pinfunction "CLR_1") (pintype "input"))
      (node (ref "E9") (pin "8") (pinfunction "O_8") (pintype "output"))
    )
    (net (code "70") (name "Net-(E14B-CLR)") (class "Default")
      (node (ref "E14") (pin "13") (pinfunction "CLR_13") (pintype "input"))
      (node (ref "U$2") (pin "BR2") (pinfunction "1_BR2") (pintype "bidirectional"))
    )
    (net (code "71") (name "Net-(E15A-I1)") (class "Default")
      (node (ref "E15") (pin "2") (pinfunction "I1_2") (pintype "input"))
      (node (ref "U$2") (pin "BU1") (pinfunction "1_BU1") (pintype "bidirectional"))
    )
    (net (code "72") (name "Net-(E15B-O)") (class "Default")
      (node (ref "C24") (pin "1") (pinfunction "1_1") (pintype "passive"))
      (node (ref "E15") (pin "6") (pinfunction "O_6") (pintype "output"))
      (node (ref "R8") (pin "1") (pinfunction "1_1") (pintype "passive"))
    )
    (net (code "73") (name "Net-(E15C-I0)") (class "Default")
      (node (ref "C24") (pin "2") (pinfunction "2_2") (pintype "passive"))
      (node (ref "D6") (pin "C") (pinfunction "C_C") (pintype "passive"))
      (node (ref "E15") (pin "10") (pinfunction "I1_10") (pintype "input"))
      (node (ref "E15") (pin "9") (pinfunction "I0_9") (pintype "input"))
      (node (ref "R7") (pin "2") (pinfunction "2_2") (pintype "passive"))
    )
    (net (code "74") (name "Net-(E15C-O)") (class "Default")
      (node (ref "E15") (pin "8") (pinfunction "O_8") (pintype "output"))
      (node (ref "E19") (pin "1") (pinfunction "I0_1") (pintype "input"))
      (node (ref "E19") (pin "2") (pinfunction "I1_2") (pintype "input"))
      (node (ref "E19") (pin "4") (pinfunction "I2_4") (pintype "input"))
      (node (ref "E19") (pin "5") (pinfunction "I3_5") (pintype "input"))
    )
    (net (code "75") (name "Net-(E15D-O)") (class "Default")
      (node (ref "E15") (pin "11") (pinfunction "O_11") (pintype "output"))
      (node (ref "E16") (pin "1") (pinfunction "CLR_1") (pintype "input"))
      (node (ref "E16") (pin "13") (pinfunction "CLR_13") (pintype "input"))
      (node (ref "E20") (pin "12") (pinfunction "I0_12") (pintype "input"))
      (node (ref "E20") (pin "13") (pinfunction "I1_13") (pintype "input"))
      (node (ref "E20") (pin "2") (pinfunction "I1_2") (pintype "input"))
    )
    (net (code "76") (name "Net-(E16A-CLK)") (class "Default")
      (node (ref "E16") (pin "12") (pinfunction "D_12") (pintype "input"))
      (node (ref "E16") (pin "3") (pinfunction "CLK_3") (pintype "input"))
      (node (ref "E16") (pin "8") (pinfunction "~{Q}_8") (pintype "output"))
    )
    (net (code "77") (name "Net-(E16A-D)") (class "Default")
      (node (ref "E16") (pin "2") (pinfunction "D_2") (pintype "input"))
      (node (ref "E16") (pin "6") (pinfunction "~{Q}_6") (pintype "output"))
      (node (ref "U$2") (pin "BS1") (pinfunction "1_BS1") (pintype "bidirectional"))
    )
    (net (code "78") (name "Net-(E16A-Q)") (class "Default")
      (node (ref "E16") (pin "5") (pinfunction "Q_5") (pintype "output"))
      (node (ref "U$2") (pin "BT2") (pinfunction "1_BT2") (pintype "bidirectional"))
    )
    (net (code "79") (name "Net-(E16B-CLK)") (class "Default")
      (node (ref "E16") (pin "11") (pinfunction "CLK_11") (pintype "input"))
      (node (ref "E2") (pin "6") (pinfunction "~{Q}_6") (pintype "output"))
    )
    (net (code "80") (name "Net-(E17A-X)") (class "Default")
      (node (ref "E17") (pin "10") (pinfunction "X_10") (pintype "output"))
      (node (ref "E17") (pin "11") (pinfunction "X_11") (pintype "output"))
      (node (ref "R5") (pin "2") (pinfunction "2_2") (pintype "passive"))
    )
    (net (code "81") (name "Net-(E17A-~{X})") (class "Default")
      (node (ref "E17") (pin "12") (pinfunction "~{X}_12") (pintype "output"))
      (node (ref "E17") (pin "4") (pinfunction "A_4") (pintype "input"))
      (node (ref "E17") (pin "5") (pinfunction "B_5") (pintype "input"))
      (node (ref "E17") (pin "6") (pinfunction "C_6") (pintype "input"))
      (node (ref "E17") (pin "8") (pinfunction "D_8") (pintype "input"))
    )
    (net (code "82") (name "Net-(E18A-CLK)") (class "Default")
      (node (ref "E18") (pin "11") (pinfunction "CLK_11") (pintype "input"))
      (node (ref "E18") (pin "3") (pinfunction "CLK_3") (pintype "input"))
      (node (ref "U$2") (pin "BP2") (pinfunction "1_BP2") (pintype "bidirectional"))
    )
    (net (code "83") (name "Net-(E18A-PRE)") (class "Default")
      (node (ref "E18") (pin "10") (pinfunction "PRE_10") (pintype "input"))
      (node (ref "E18") (pin "4") (pinfunction "PRE_4") (pintype "input"))
      (node (ref "U$2") (pin "BP1") (pinfunction "1_BP1") (pintype "bidirectional"))
    )
    (net (code "84") (name "Net-(E18A-Q)") (class "Default")
      (node (ref "E18") (pin "12") (pinfunction "D_12") (pintype "input"))
      (node (ref "E18") (pin "5") (pinfunction "Q_5") (pintype "output"))
    )
    (net (code "85") (name "Net-(E18A-~{Q})") (class "Default")
      (node (ref "E18") (pin "6") (pinfunction "~{Q}_6") (pintype "output"))
      (node (ref "U$2") (pin "BU2") (pinfunction "1_BU2") (pintype "bidirectional"))
    )
    (net (code "86") (name "Net-(E18B-~{Q})") (class "Default")
      (node (ref "E18") (pin "8") (pinfunction "~{Q}_8") (pintype "output"))
      (node (ref "U$2") (pin "BV2") (pinfunction "1_BV2") (pintype "bidirectional"))
    )
    (net (code "87") (name "Net-(E19B-I1)") (class "Default")
      (node (ref "E19") (pin "10") (pinfunction "I1_10") (pintype "input"))
      (node (ref "E20") (pin "11") (pinfunction "O_11") (pintype "output"))
    )
    (net (code "88") (name "Net-(E20A-I0)") (class "Default")
      (node (ref "E2") (pin "5") (pinfunction "Q_5") (pintype "output"))
      (node (ref "E20") (pin "1") (pinfunction "I0_1") (pintype "input"))
    )
    (net (code "89") (name "Net-(E20A-O)") (class "Default")
      (node (ref "E2") (pin "2") (pinfunction "D_2") (pintype "input"))
      (node (ref "E20") (pin "3") (pinfunction "O_3") (pintype "output"))
    )
    (net (code "90") (name "Net-(E20B-I0)") (class "Default")
      (node (ref "E20") (pin "4") (pinfunction "I0_4") (pintype "input"))
      (node (ref "U$2") (pin "BM1") (pinfunction "1_BM1") (pintype "bidirectional"))
    )
    (net (code "91") (name "Net-(E20B-O)") (class "Default")
      (node (ref "E20") (pin "6") (pinfunction "O_6") (pintype "output"))
      (node (ref "U$2") (pin "BN1") (pinfunction "1_BN1") (pintype "bidirectional"))
    )
    (net (code "92") (name "Net-(Q1-E)") (class "Default")
      (node (ref "D5") (pin "A") (pinfunction "A_A") (pintype "passive"))
      (node (ref "Q1") (pin "1") (pinfunction "E_1") (pintype "passive"))
      (node (ref "R6") (pin "1") (pinfunction "1_1") (pintype "passive"))
    )
    (net (code "93") (name "VCC") (class "Default")
      (node (ref "C1") (pin "1") (pinfunction "1_1") (pintype "passive"))
      (node (ref "C10") (pin "1") (pinfunction "1_1") (pintype "passive"))
      (node (ref "C11") (pin "1") (pinfunction "1_1") (pintype "passive"))
      (node (ref "C12") (pin "1") (pinfunction "1_1") (pintype "passive"))
      (node (ref "C13") (pin "1") (pinfunction "1_1") (pintype "passive"))
      (node (ref "C14") (pin "1") (pinfunction "1_1") (pintype "passive"))
      (node (ref "C15") (pin "1") (pinfunction "1_1") (pintype "passive"))
      (node (ref "C16") (pin "1") (pinfunction "1_1") (pintype "passive"))
      (node (ref "C17") (pin "1") (pinfunction "1_1") (pintype "passive"))
      (node (ref "C18") (pin "1") (pinfunction "1_1") (pintype "passive"))
      (node (ref "C19") (pin "1") (pinfunction "1_1") (pintype "passive"))
      (node (ref "C2") (pin "1") (pinfunction "1_1") (pintype "passive"))
      (node (ref "C20") (pin "1") (pinfunction "1_1") (pintype "passive"))
      (node (ref "C21") (pin "1") (pinfunction "1_1") (pintype "passive"))
      (node (ref "C22") (pin "1") (pinfunction "1_1") (pintype "passive"))
      (node (ref "C23") (pin "1") (pinfunction "1_1") (pintype "passive"))
      (node (ref "C3") (pin "1") (pinfunction "1_1") (pintype "passive"))
      (node (ref "C4") (pin "1") (pinfunction "1_1") (pintype "passive"))
      (node (ref "C5") (pin "1") (pinfunction "1_1") (pintype "passive"))
      (node (ref "C6") (pin "1") (pinfunction "1_1") (pintype "passive"))
      (node (ref "C7") (pin "1") (pinfunction "1_1") (pintype "passive"))
      (node (ref "C8") (pin "1") (pinfunction "1_1") (pintype "passive"))
      (node (ref "C9") (pin "1") (pinfunction "1_1") (pintype "passive"))
      (node (ref "D2") (pin "C") (pinfunction "C_C") (pintype "passive"))
      (node (ref "R2") (pin "2") (pinfunction "2_2") (pintype "passive"))
      (node (ref "R3") (pin "2") (pinfunction "2_2") (pintype "passive"))
      (node (ref "R4") (pin "2") (pinfunction "2_2") (pintype "passive"))
      (node (ref "R6") (pin "2") (pinfunction "2_2") (pintype "passive"))
      (node (ref "R8") (pin "2") (pinfunction "2_2") (pintype "passive"))
      (node (ref "U$2") (pin "AA2") (pinfunction "1_AA2") (pintype "bidirectional"))
      (node (ref "U$2") (pin "BA2") (pinfunction "1_BA2") (pintype "bidirectional"))
    )
    (net (code "94") (name "unconnected-(E5B-~{Q}-Pad8)") (class "Default")
      (node (ref "E5") (pin "8") (pinfunction "~{Q}_8") (pintype "output"))
    )
    (net (code "95") (name "unconnected-(E6A-~{Q}-Pad6)") (class "Default")
      (node (ref "E6") (pin "6") (pinfunction "~{Q}_6") (pintype "output"))
    )
    (net (code "96") (name "unconnected-(E6B-~{Q}-Pad8)") (class "Default")
      (node (ref "E6") (pin "8") (pinfunction "~{Q}_8") (pintype "output"))
    )
    (net (code "97") (name "unconnected-(E8A-~{Q}-Pad6)") (class "Default")
      (node (ref "E8") (pin "6") (pinfunction "~{Q}_6") (pintype "output"))
    )
    (net (code "98") (name "unconnected-(E8B-~{Q}-Pad8)") (class "Default")
      (node (ref "E8") (pin "8") (pinfunction "~{Q}_8") (pintype "output"))
    )
    (net (code "99") (name "unconnected-(E10A-~{Q}-Pad6)") (class "Default")
      (node (ref "E10") (pin "6") (pinfunction "~{Q}_6") (pintype "output"))
    )
    (net (code "100") (name "unconnected-(E10B-~{Q}-Pad8)") (class "Default")
      (node (ref "E10") (pin "8") (pinfunction "~{Q}_8") (pintype "output"))
    )
    (net (code "101") (name "unconnected-(E13B-~{Q}-Pad8)") (class "Default")
      (node (ref "E13") (pin "8") (pinfunction "~{Q}_8") (pintype "output"))
    )
    (net (code "102") (name "unconnected-(E16B-Q-Pad9)") (class "Default")
      (node (ref "E16") (pin "9") (pinfunction "Q_9") (pintype "output"))
    )
    (net (code "103") (name "unconnected-(E18B-Q-Pad9)") (class "Default")
      (node (ref "E18") (pin "9") (pinfunction "Q_9") (pintype "output"))
    )
  )
)
